# uC_Sensor.net
KiCad netlist of a schematic drawn in EAGLE
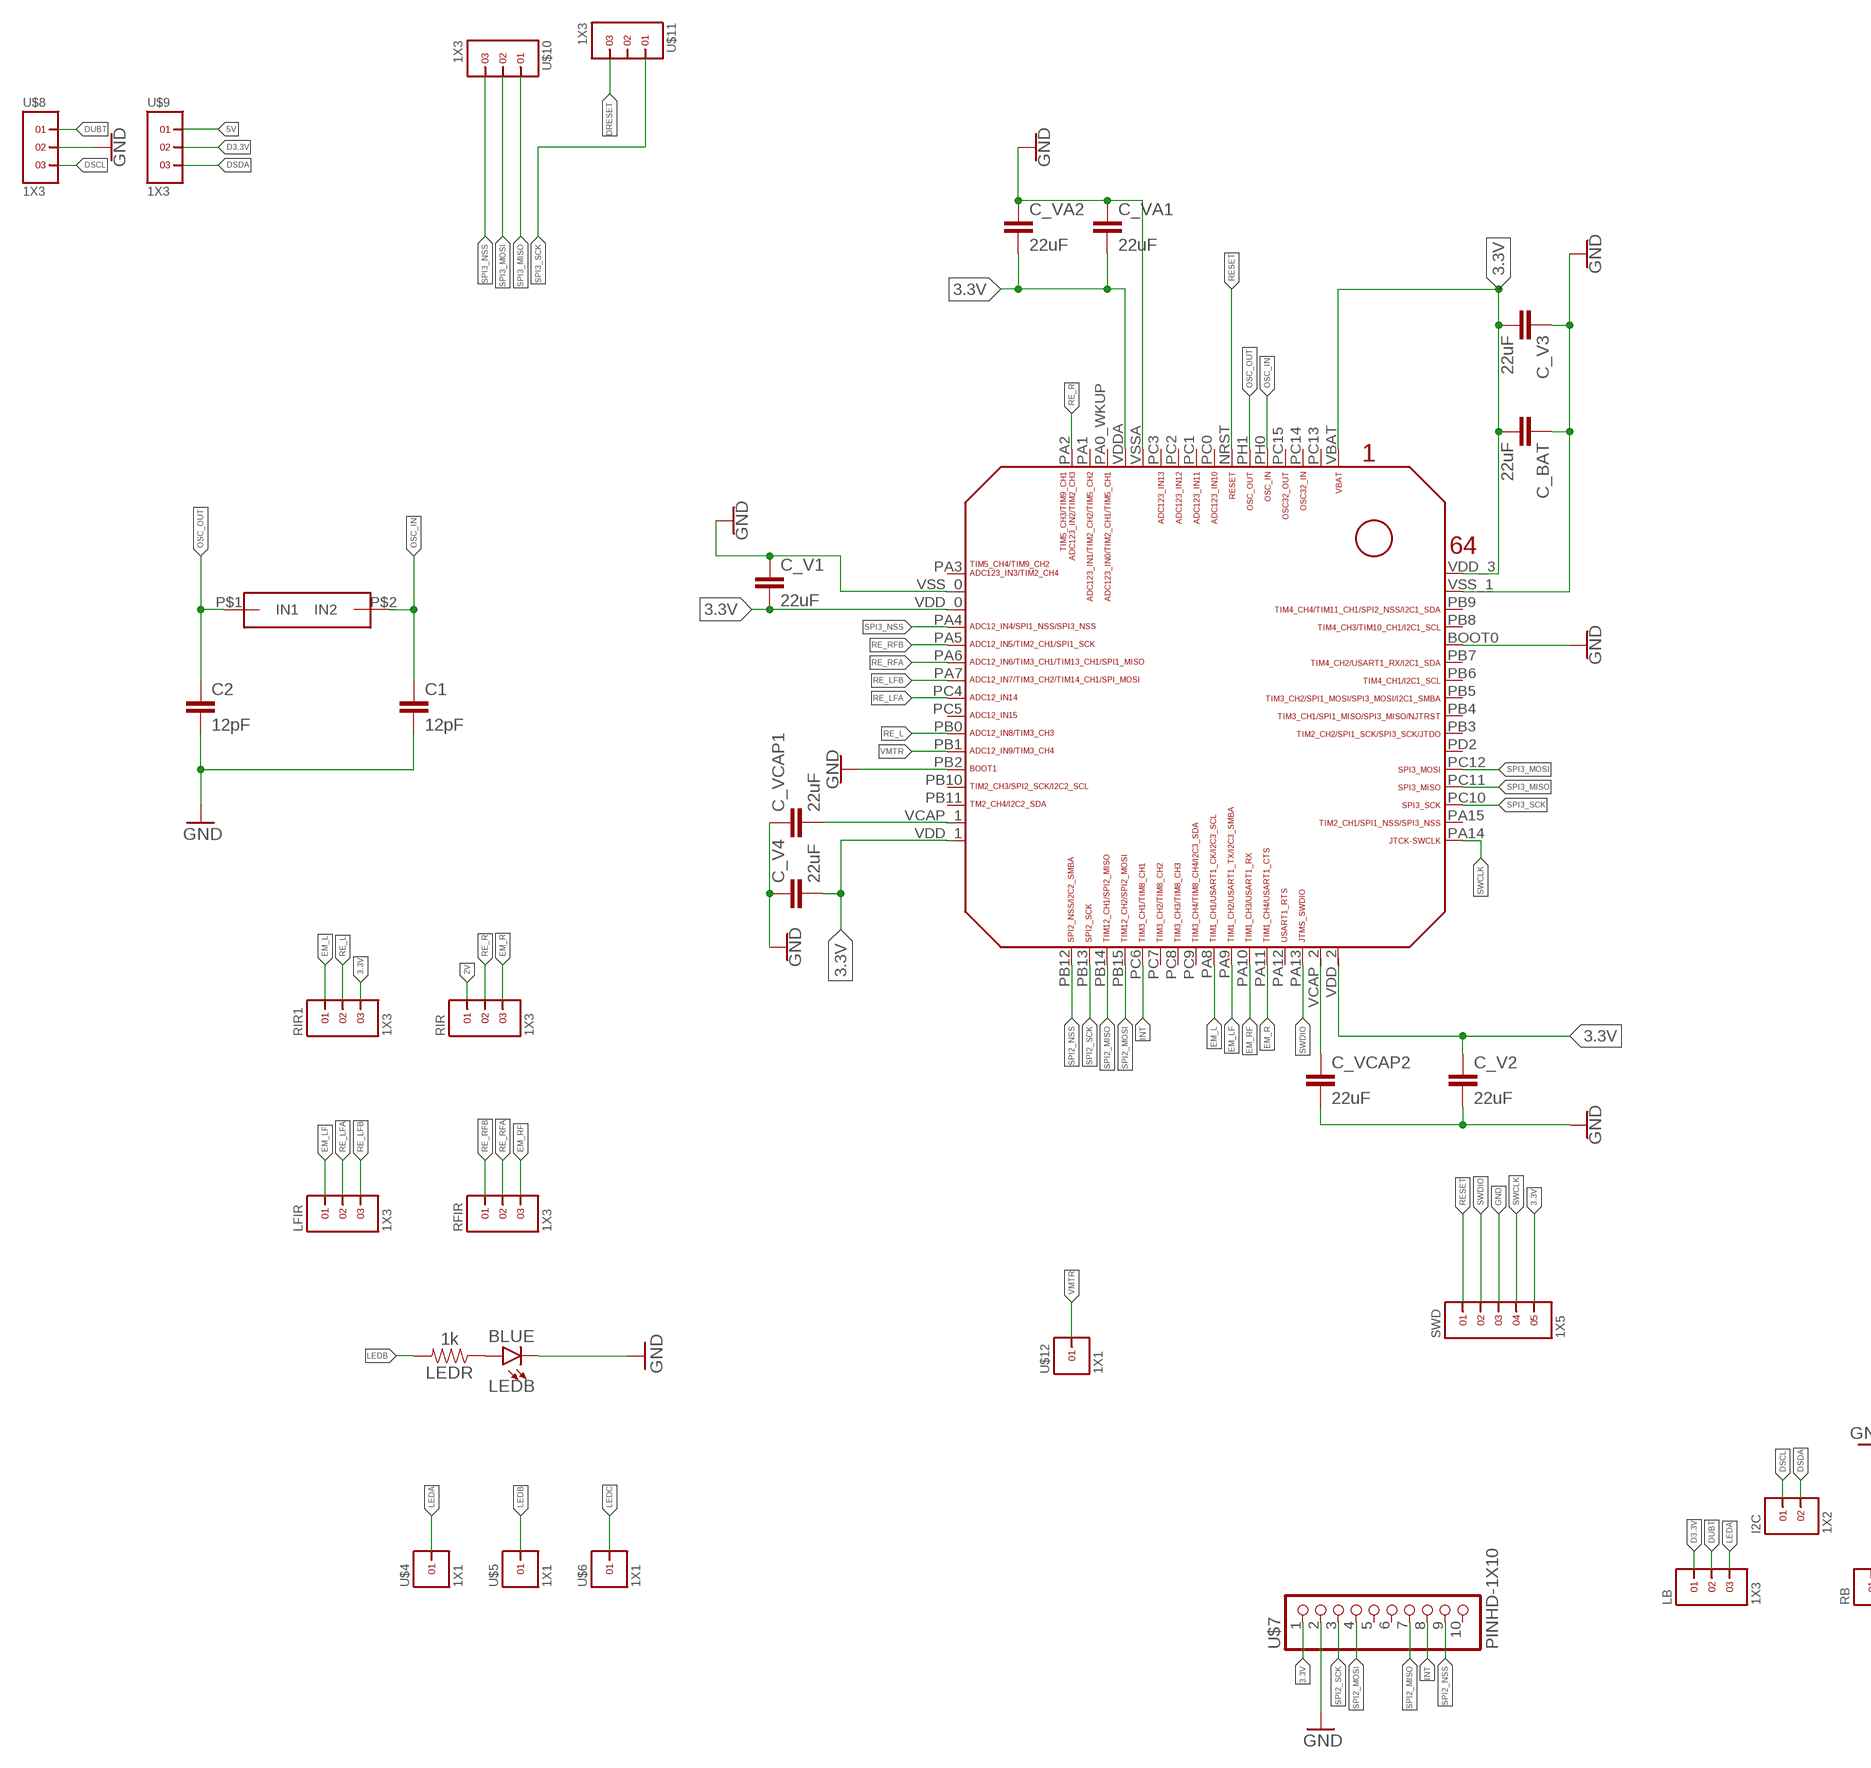
[diagram p0: schematic, sheet 1, part 1 of 2]
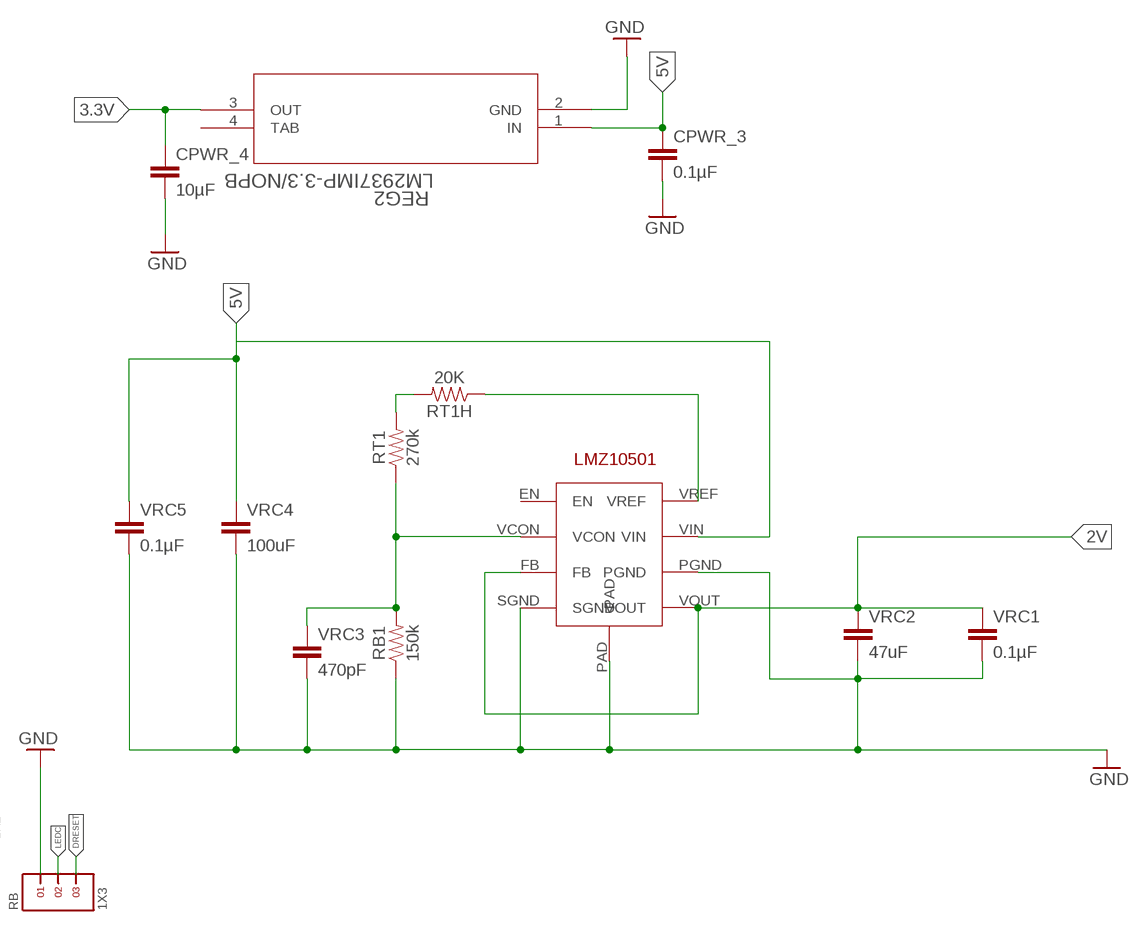
[diagram p1: schematic, sheet 1, part 2 of 2]

(export (version "E")
  (design (tool "Eeschema 10.0.6"))
  (components
    (comp (ref "C1")
      (value "12pF")
      (footprint "eagle-import:0603")
      (libsource (lib "eagle-import") (part "22PF-0603-50V-5%"))
    )
    (comp (ref "C2")
      (value "12pF")
      (footprint "eagle-import:0603")
      (libsource (lib "eagle-import") (part "22PF-0603-50V-5%"))
    )
    (comp (ref "CPWR_3")
      (value "0.1µF")
      (footprint "eagle-import:0805@2")
      (libsource (lib "eagle-import") (part "0.33UF/330NF-0805-50V-10%"))
    )
    (comp (ref "CPWR_4")
      (value "10µF")
      (footprint "eagle-import:0805@2")
      (libsource (lib "eagle-import") (part "0.33UF/330NF-0805-50V-10%"))
    )
    (comp (ref "C_BAT")
      (value "22uF")
      (footprint "eagle-import:0805")
      (libsource (lib "eagle-import") (part "22UF-0805-6.3V-20%"))
    )
    (comp (ref "C_V1")
      (value "22uF")
      (footprint "eagle-import:0805")
      (libsource (lib "eagle-import") (part "22UF-0805-6.3V-20%"))
    )
    (comp (ref "C_V2")
      (value "22uF")
      (footprint "eagle-import:0805")
      (libsource (lib "eagle-import") (part "22UF-0805-6.3V-20%"))
    )
    (comp (ref "C_V3")
      (value "22uF")
      (footprint "eagle-import:0805")
      (libsource (lib "eagle-import") (part "22UF-0805-6.3V-20%"))
    )
    (comp (ref "C_V4")
      (value "22uF")
      (footprint "eagle-import:0805")
      (libsource (lib "eagle-import") (part "22UF-0805-6.3V-20%"))
    )
    (comp (ref "C_VA1")
      (value "22uF")
      (footprint "eagle-import:0805")
      (libsource (lib "eagle-import") (part "22UF-0805-6.3V-20%"))
    )
    (comp (ref "C_VA2")
      (value "22uF")
      (footprint "eagle-import:0805")
      (libsource (lib "eagle-import") (part "22UF-0805-6.3V-20%"))
    )
    (comp (ref "C_VCAP1")
      (value "22uF")
      (footprint "eagle-import:0805")
      (libsource (lib "eagle-import") (part "22UF-0805-6.3V-20%"))
    )
    (comp (ref "C_VCAP2")
      (value "22uF")
      (footprint "eagle-import:0805")
      (libsource (lib "eagle-import") (part "22UF-0805-6.3V-20%"))
    )
    (comp (ref "I2C")
      (value "1X2")
      (footprint "eagle-import:1X2")
      (libsource (lib "eagle-import") (part "1X2"))
    )
    (comp (ref "LB")
      (value "1X3")
      (footprint "eagle-import:1X3")
      (libsource (lib "eagle-import") (part "1X3"))
    )
    (comp (ref "LEDB")
      (value "BLUE")
      (footprint "eagle-import:LED-1206")
      (libsource (lib "eagle-import") (part "LED-BLUE1206"))
    )
    (comp (ref "LEDR")
      (value "1k")
      (footprint "eagle-import:0805")
      (libsource (lib "eagle-import") (part "0.75OHM-0805-1/4W-1%"))
    )
    (comp (ref "LFIR")
      (value "1X3")
      (footprint "eagle-import:1X3")
      (libsource (lib "eagle-import") (part "1X3"))
    )
    (comp (ref "RB")
      (value "1X3")
      (footprint "eagle-import:1X3")
      (libsource (lib "eagle-import") (part "1X3"))
    )
    (comp (ref "RB1")
      (value "150k")
      (footprint "eagle-import:0805")
      (libsource (lib "eagle-import") (part "SparkFun-Resistors_532_0.75OHM-0805-1/4W-1%"))
    )
    (comp (ref "REG2")
      (value "LM2937IMP-3.3/NOPB")
      (footprint "eagle-import:MP04A")
      (fields
        (field (name "MANUFACTURER_PART_NUMBER") "lm2937imp3_3nopb")
        (field (name "COPYRIGHT") "Copyright C 2015 Accelerated Designs. All rights reserved")
      )
      (libsource (lib "eagle-import") (part "LM2937IMP-3.3/NOPB"))
    )
    (comp (ref "RFIR")
      (value "1X3")
      (footprint "eagle-import:1X3")
      (libsource (lib "eagle-import") (part "1X3"))
    )
    (comp (ref "RIR")
      (value "1X3")
      (footprint "eagle-import:1X3")
      (libsource (lib "eagle-import") (part "1X3"))
    )
    (comp (ref "RIR1")
      (value "1X3")
      (footprint "eagle-import:1X3")
      (libsource (lib "eagle-import") (part "1X3"))
    )
    (comp (ref "RT1")
      (value "270k")
      (footprint "eagle-import:0805")
      (libsource (lib "eagle-import") (part "SparkFun-Resistors_532_0.75OHM-0805-1/4W-1%"))
    )
    (comp (ref "RT1H")
      (value "20K")
      (footprint "eagle-import:0805")
      (libsource (lib "eagle-import") (part "SparkFun-Resistors_532_0.75OHM-0805-1/4W-1%"))
    )
    (comp (ref "SWD")
      (value "1X5")
      (footprint "eagle-import:1X5")
      (libsource (lib "eagle-import") (part "1X5"))
    )
    (comp (ref "U$1")
      (value "STM32F405/415_LQFP64")
      (footprint "eagle-import:STM32F405_415_LQFP64")
      (libsource (lib "eagle-import") (part "STM32F405/415_LQFP64"))
    )
    (comp (ref "U$2")
      (value "OSC")
      (footprint "eagle-import:OSC")
      (libsource (lib "eagle-import") (part "OSC"))
    )
    (comp (ref "U$3")
      (value "LMZ10501")
      (footprint "eagle-import:LMZ10501")
      (libsource (lib "eagle-import") (part "LMZ10501"))
    )
    (comp (ref "U$4")
      (value "1X1")
      (footprint "eagle-import:1X1")
      (libsource (lib "eagle-import") (part "1X1"))
    )
    (comp (ref "U$5")
      (value "1X1")
      (footprint "eagle-import:1X1")
      (libsource (lib "eagle-import") (part "1X1"))
    )
    (comp (ref "U$6")
      (value "1X1")
      (footprint "eagle-import:1X1")
      (libsource (lib "eagle-import") (part "1X1"))
    )
    (comp (ref "U$7")
      (value "PINHD-1X10")
      (footprint "eagle-import:1X10-BIG")
      (libsource (lib "eagle-import") (part "PINHD-1X10"))
    )
    (comp (ref "U$8")
      (value "1X3")
      (footprint "eagle-import:1X3")
      (libsource (lib "eagle-import") (part "1X3"))
    )
    (comp (ref "U$9")
      (value "1X3")
      (footprint "eagle-import:1X3")
      (libsource (lib "eagle-import") (part "1X3"))
    )
    (comp (ref "U$10")
      (value "1X3")
      (footprint "eagle-import:1X3")
      (libsource (lib "eagle-import") (part "1X3"))
    )
    (comp (ref "U$11")
      (value "1X3")
      (footprint "eagle-import:1X3")
      (libsource (lib "eagle-import") (part "1X3"))
    )
    (comp (ref "U$12")
      (value "1X1")
      (footprint "eagle-import:1X1")
      (libsource (lib "eagle-import") (part "1X1"))
    )
    (comp (ref "VRC1")
      (value "0.1µF")
      (footprint "eagle-import:0805@2")
      (libsource (lib "eagle-import") (part "0.33UF/330NF-0805-50V-10%"))
    )
    (comp (ref "VRC2")
      (value "47uF")
      (footprint "eagle-import:0805@2")
      (libsource (lib "eagle-import") (part "0.33UF/330NF-0805-50V-10%"))
    )
    (comp (ref "VRC3")
      (value "470pF")
      (footprint "eagle-import:0805@2")
      (libsource (lib "eagle-import") (part "0.33UF/330NF-0805-50V-10%"))
    )
    (comp (ref "VRC4")
      (value "100uF")
      (footprint "eagle-import:0805@2")
      (libsource (lib "eagle-import") (part "0.33UF/330NF-0805-50V-10%"))
    )
    (comp (ref "VRC5")
      (value "0.1µF")
      (footprint "eagle-import:0805@2")
      (libsource (lib "eagle-import") (part "0.33UF/330NF-0805-50V-10%"))
    )
  )
  (nets
    (net (code "1") (name "/TAB") (class "Default")
      (node (ref "REG2") (pin "4") (pinfunction "TAB_4") (pintype "power_in"))
    )
    (net (code "2") (name "2V") (class "Default")
      (node (ref "RIR") (pin "1") (pinfunction "1_1") (pintype "bidirectional"))
      (node (ref "U$3") (pin "FB") (pinfunction "FB_FB") (pintype "bidirectional"))
      (node (ref "U$3") (pin "VOUT") (pinfunction "VOUT_VOUT") (pintype "bidirectional"))
      (node (ref "VRC1") (pin "1") (pinfunction "1_1") (pintype "passive"))
      (node (ref "VRC2") (pin "1") (pinfunction "1_1") (pintype "passive"))
    )
    (net (code "3") (name "3.3V") (class "Default")
      (node (ref "CPWR_4") (pin "1") (pinfunction "1_1") (pintype "passive"))
      (node (ref "C_BAT") (pin "2") (pinfunction "2_2") (pintype "passive"))
      (node (ref "C_V1") (pin "2") (pinfunction "2_2") (pintype "passive"))
      (node (ref "C_V2") (pin "1") (pinfunction "1_1") (pintype "passive"))
      (node (ref "C_V3") (pin "2") (pinfunction "2_2") (pintype "passive"))
      (node (ref "C_V4") (pin "2") (pinfunction "2_2") (pintype "passive"))
      (node (ref "C_VA1") (pin "2") (pinfunction "2_2") (pintype "passive"))
      (node (ref "C_VA2") (pin "2") (pinfunction "2_2") (pintype "passive"))
      (node (ref "REG2") (pin "3") (pinfunction "OUT_3") (pintype "power_in"))
      (node (ref "RIR1") (pin "3") (pinfunction "3_3") (pintype "bidirectional"))
      (node (ref "SWD") (pin "5") (pinfunction "5_5") (pintype "bidirectional"))
      (node (ref "U$1") (pin "VBAT") (pinfunction "VBAT_VBAT") (pintype "bidirectional"))
      (node (ref "U$1") (pin "VDDA") (pinfunction "VDDA_VDDA") (pintype "bidirectional"))
      (node (ref "U$1") (pin "VDD_0") (pinfunction "VDD_0_VDD_0") (pintype "bidirectional"))
      (node (ref "U$1") (pin "VDD_1") (pinfunction "VDD_1_VDD_1") (pintype "bidirectional"))
      (node (ref "U$1") (pin "VDD_2") (pinfunction "VDD_2_VDD_2") (pintype "bidirectional"))
      (node (ref "U$1") (pin "VDD_3") (pinfunction "VDD_3_VDD_3") (pintype "bidirectional"))
      (node (ref "U$7") (pin "1") (pinfunction "1_1") (pintype "passive"))
    )
    (net (code "4") (name "5V") (class "Default")
      (node (ref "CPWR_3") (pin "1") (pinfunction "1_1") (pintype "passive"))
      (node (ref "REG2") (pin "1") (pinfunction "IN_1") (pintype "power_in"))
      (node (ref "U$3") (pin "VIN") (pinfunction "VIN_VIN") (pintype "bidirectional"))
      (node (ref "U$9") (pin "1") (pinfunction "1_1") (pintype "bidirectional"))
      (node (ref "VRC4") (pin "1") (pinfunction "1_1") (pintype "passive"))
      (node (ref "VRC5") (pin "1") (pinfunction "1_1") (pintype "passive"))
    )
    (net (code "5") (name "D3.3V") (class "Default")
      (node (ref "LB") (pin "1") (pinfunction "1_1") (pintype "bidirectional"))
      (node (ref "U$9") (pin "2") (pinfunction "2_2") (pintype "bidirectional"))
    )
    (net (code "6") (name "DRESET") (class "Default")
      (node (ref "RB") (pin "3") (pinfunction "3_3") (pintype "bidirectional"))
      (node (ref "U$11") (pin "3") (pinfunction "3_3") (pintype "bidirectional"))
    )
    (net (code "7") (name "DSCL") (class "Default")
      (node (ref "I2C") (pin "1") (pinfunction "1_1") (pintype "bidirectional"))
      (node (ref "U$8") (pin "3") (pinfunction "3_3") (pintype "bidirectional"))
    )
    (net (code "8") (name "DSDA") (class "Default")
      (node (ref "I2C") (pin "2") (pinfunction "2_2") (pintype "bidirectional"))
      (node (ref "U$9") (pin "3") (pinfunction "3_3") (pintype "bidirectional"))
    )
    (net (code "9") (name "DUBT") (class "Default")
      (node (ref "LB") (pin "2") (pinfunction "2_2") (pintype "bidirectional"))
      (node (ref "U$8") (pin "1") (pinfunction "1_1") (pintype "bidirectional"))
    )
    (net (code "10") (name "EM_L") (class "Default")
      (node (ref "RIR1") (pin "1") (pinfunction "1_1") (pintype "bidirectional"))
      (node (ref "U$1") (pin "PA8") (pinfunction "PA8_PA8") (pintype "bidirectional"))
    )
    (net (code "11") (name "EM_LF") (class "Default")
      (node (ref "LFIR") (pin "1") (pinfunction "1_1") (pintype "bidirectional"))
      (node (ref "U$1") (pin "PA9") (pinfunction "PA9_PA9") (pintype "bidirectional"))
    )
    (net (code "12") (name "EM_R") (class "Default")
      (node (ref "RIR") (pin "3") (pinfunction "3_3") (pintype "bidirectional"))
      (node (ref "U$1") (pin "PA11") (pinfunction "PA11_PA11") (pintype "bidirectional"))
    )
    (net (code "13") (name "EM_RF") (class "Default")
      (node (ref "RFIR") (pin "3") (pinfunction "3_3") (pintype "bidirectional"))
      (node (ref "U$1") (pin "PA10") (pinfunction "PA10_PA10") (pintype "bidirectional"))
    )
    (net (code "14") (name "GND") (class "Default")
      (node (ref "C1") (pin "2") (pinfunction "2_2") (pintype "passive"))
      (node (ref "C2") (pin "2") (pinfunction "2_2") (pintype "passive"))
      (node (ref "CPWR_3") (pin "2") (pinfunction "2_2") (pintype "passive"))
      (node (ref "CPWR_4") (pin "2") (pinfunction "2_2") (pintype "passive"))
      (node (ref "C_BAT") (pin "1") (pinfunction "1_1") (pintype "passive"))
      (node (ref "C_V1") (pin "1") (pinfunction "1_1") (pintype "passive"))
      (node (ref "C_V2") (pin "2") (pinfunction "2_2") (pintype "passive"))
      (node (ref "C_V3") (pin "1") (pinfunction "1_1") (pintype "passive"))
      (node (ref "C_V4") (pin "1") (pinfunction "1_1") (pintype "passive"))
      (node (ref "C_VA1") (pin "1") (pinfunction "1_1") (pintype "passive"))
      (node (ref "C_VA2") (pin "1") (pinfunction "1_1") (pintype "passive"))
      (node (ref "C_VCAP1") (pin "1") (pinfunction "1_1") (pintype "passive"))
      (node (ref "C_VCAP2") (pin "2") (pinfunction "2_2") (pintype "passive"))
      (node (ref "LEDB") (pin "C") (pinfunction "C_C") (pintype "passive"))
      (node (ref "RB") (pin "1") (pinfunction "1_1") (pintype "bidirectional"))
      (node (ref "RB1") (pin "1") (pinfunction "1_1") (pintype "passive"))
      (node (ref "REG2") (pin "2") (pinfunction "GND_2") (pintype "power_in"))
      (node (ref "SWD") (pin "3") (pinfunction "3_3") (pintype "bidirectional"))
      (node (ref "U$1") (pin "BOOT0") (pinfunction "BOOT0_BOOT0") (pintype "bidirectional"))
      (node (ref "U$1") (pin "PB2") (pinfunction "PB2_PB2") (pintype "bidirectional"))
      (node (ref "U$1") (pin "VSSA") (pinfunction "VSSA_VSSA") (pintype "bidirectional"))
      (node (ref "U$1") (pin "VSS_0") (pinfunction "VSS_0_VSS_0") (pintype "bidirectional"))
      (node (ref "U$1") (pin "VSS_1") (pinfunction "VSS_1_VSS_1") (pintype "bidirectional"))
      (node (ref "U$3") (pin "PAD") (pinfunction "PAD_PAD") (pintype "bidirectional"))
      (node (ref "U$3") (pin "PGND") (pinfunction "PGND_PGND") (pintype "bidirectional"))
      (node (ref "U$3") (pin "SGND") (pinfunction "SGND_SGND") (pintype "bidirectional"))
      (node (ref "U$7") (pin "2") (pinfunction "2_2") (pintype "passive"))
      (node (ref "U$8") (pin "2") (pinfunction "2_2") (pintype "bidirectional"))
      (node (ref "VRC1") (pin "2") (pinfunction "2_2") (pintype "passive"))
      (node (ref "VRC2") (pin "2") (pinfunction "2_2") (pintype "passive"))
      (node (ref "VRC3") (pin "2") (pinfunction "2_2") (pintype "passive"))
      (node (ref "VRC4") (pin "2") (pinfunction "2_2") (pintype "passive"))
      (node (ref "VRC5") (pin "2") (pinfunction "2_2") (pintype "passive"))
    )
    (net (code "15") (name "INT") (class "Default")
      (node (ref "U$1") (pin "PC6") (pinfunction "PC6_PC6") (pintype "bidirectional"))
      (node (ref "U$7") (pin "8") (pinfunction "8_8") (pintype "passive"))
    )
    (net (code "16") (name "LEDA") (class "Default")
      (node (ref "LB") (pin "3") (pinfunction "3_3") (pintype "bidirectional"))
      (node (ref "U$4") (pin "1") (pinfunction "1_1") (pintype "bidirectional"))
    )
    (net (code "17") (name "LEDB") (class "Default")
      (node (ref "LEDR") (pin "2") (pinfunction "2_2") (pintype "passive"))
      (node (ref "U$5") (pin "1") (pinfunction "1_1") (pintype "bidirectional"))
    )
    (net (code "18") (name "LEDC") (class "Default")
      (node (ref "RB") (pin "2") (pinfunction "2_2") (pintype "bidirectional"))
      (node (ref "U$6") (pin "1") (pinfunction "1_1") (pintype "bidirectional"))
    )
    (net (code "19") (name "Net-(C_VCAP1-Pad2)") (class "Default")
      (node (ref "C_VCAP1") (pin "2") (pinfunction "2_2") (pintype "passive"))
      (node (ref "U$1") (pin "VCAP_1") (pinfunction "VCAP_1_VCAP_1") (pintype "bidirectional"))
    )
    (net (code "20") (name "Net-(C_VCAP2-Pad1)") (class "Default")
      (node (ref "C_VCAP2") (pin "1") (pinfunction "1_1") (pintype "passive"))
      (node (ref "U$1") (pin "VCAP_2") (pinfunction "VCAP_2_VCAP_2") (pintype "bidirectional"))
    )
    (net (code "21") (name "Net-(LEDB-PadA)") (class "Default")
      (node (ref "LEDB") (pin "A") (pinfunction "A_A") (pintype "passive"))
      (node (ref "LEDR") (pin "1") (pinfunction "1_1") (pintype "passive"))
    )
    (net (code "22") (name "Net-(RB1-Pad2)") (class "Default")
      (node (ref "RB1") (pin "2") (pinfunction "2_2") (pintype "passive"))
      (node (ref "RT1") (pin "1") (pinfunction "1_1") (pintype "passive"))
      (node (ref "U$3") (pin "VCON") (pinfunction "VCON_VCON") (pintype "bidirectional"))
      (node (ref "VRC3") (pin "1") (pinfunction "1_1") (pintype "passive"))
    )
    (net (code "23") (name "Net-(RT1-Pad2)") (class "Default")
      (node (ref "RT1") (pin "2") (pinfunction "2_2") (pintype "passive"))
      (node (ref "RT1H") (pin "2") (pinfunction "2_2") (pintype "passive"))
    )
    (net (code "24") (name "Net-(RT1H-Pad1)") (class "Default")
      (node (ref "RT1H") (pin "1") (pinfunction "1_1") (pintype "passive"))
      (node (ref "U$3") (pin "VREF") (pinfunction "VREF_VREF") (pintype "bidirectional"))
    )
    (net (code "25") (name "OSC_IN") (class "Default")
      (node (ref "C1") (pin "1") (pinfunction "1_1") (pintype "passive"))
      (node (ref "U$1") (pin "PH0") (pinfunction "PH0_PH0") (pintype "bidirectional"))
      (node (ref "U$2") (pin "P$2") (pinfunction "IN2_P$2") (pintype "bidirectional"))
    )
    (net (code "26") (name "OSC_OUT") (class "Default")
      (node (ref "C2") (pin "1") (pinfunction "1_1") (pintype "passive"))
      (node (ref "U$1") (pin "PH1") (pinfunction "PH1_PH1") (pintype "bidirectional"))
      (node (ref "U$2") (pin "P$1") (pinfunction "IN1_P$1") (pintype "bidirectional"))
    )
    (net (code "27") (name "RESET") (class "Default")
      (node (ref "SWD") (pin "1") (pinfunction "1_1") (pintype "bidirectional"))
      (node (ref "U$1") (pin "NRST") (pinfunction "NRST_NRST") (pintype "bidirectional"))
    )
    (net (code "28") (name "RE_L") (class "Default")
      (node (ref "RIR1") (pin "2") (pinfunction "2_2") (pintype "bidirectional"))
      (node (ref "U$1") (pin "PB0") (pinfunction "PB0_PB0") (pintype "bidirectional"))
    )
    (net (code "29") (name "RE_LFA") (class "Default")
      (node (ref "LFIR") (pin "2") (pinfunction "2_2") (pintype "bidirectional"))
      (node (ref "U$1") (pin "PC4") (pinfunction "PC4_PC4") (pintype "bidirectional"))
    )
    (net (code "30") (name "RE_LFB") (class "Default")
      (node (ref "LFIR") (pin "3") (pinfunction "3_3") (pintype "bidirectional"))
      (node (ref "U$1") (pin "PA7") (pinfunction "PA7_PA7") (pintype "bidirectional"))
    )
    (net (code "31") (name "RE_R") (class "Default")
      (node (ref "RIR") (pin "2") (pinfunction "2_2") (pintype "bidirectional"))
      (node (ref "U$1") (pin "PA2") (pinfunction "PA2_PA2") (pintype "bidirectional"))
    )
    (net (code "32") (name "RE_RFA") (class "Default")
      (node (ref "RFIR") (pin "2") (pinfunction "2_2") (pintype "bidirectional"))
      (node (ref "U$1") (pin "PA6") (pinfunction "PA6_PA6") (pintype "bidirectional"))
    )
    (net (code "33") (name "RE_RFB") (class "Default")
      (node (ref "RFIR") (pin "1") (pinfunction "1_1") (pintype "bidirectional"))
      (node (ref "U$1") (pin "PA5") (pinfunction "PA5_PA5") (pintype "bidirectional"))
    )
    (net (code "34") (name "SPI2_MISO") (class "Default")
      (node (ref "U$1") (pin "PB14") (pinfunction "PB14_PB14") (pintype "bidirectional"))
      (node (ref "U$7") (pin "7") (pinfunction "7_7") (pintype "passive"))
    )
    (net (code "35") (name "SPI2_MOSI") (class "Default")
      (node (ref "U$1") (pin "PB15") (pinfunction "PB15_PB15") (pintype "bidirectional"))
      (node (ref "U$7") (pin "4") (pinfunction "4_4") (pintype "passive"))
    )
    (net (code "36") (name "SPI2_NSS") (class "Default")
      (node (ref "U$1") (pin "PB12") (pinfunction "PB12_PB12") (pintype "bidirectional"))
      (node (ref "U$7") (pin "9") (pinfunction "9_9") (pintype "passive"))
    )
    (net (code "37") (name "SPI2_SCK") (class "Default")
      (node (ref "U$1") (pin "PB13") (pinfunction "PB13_PB13") (pintype "bidirectional"))
      (node (ref "U$7") (pin "3") (pinfunction "3_3") (pintype "passive"))
    )
    (net (code "38") (name "SPI3_MISO") (class "Default")
      (node (ref "U$1") (pin "PC11") (pinfunction "PC11_PC11") (pintype "bidirectional"))
      (node (ref "U$10") (pin "1") (pinfunction "1_1") (pintype "bidirectional"))
    )
    (net (code "39") (name "SPI3_MOSI") (class "Default")
      (node (ref "U$1") (pin "PC12") (pinfunction "PC12_PC12") (pintype "bidirectional"))
      (node (ref "U$10") (pin "2") (pinfunction "2_2") (pintype "bidirectional"))
    )
    (net (code "40") (name "SPI3_NSS") (class "Default")
      (node (ref "U$1") (pin "PA4") (pinfunction "PA4_PA4") (pintype "bidirectional"))
      (node (ref "U$10") (pin "3") (pinfunction "3_3") (pintype "bidirectional"))
    )
    (net (code "41") (name "SPI3_SCK") (class "Default")
      (node (ref "U$1") (pin "PC10") (pinfunction "PC10_PC10") (pintype "bidirectional"))
      (node (ref "U$11") (pin "1") (pinfunction "1_1") (pintype "bidirectional"))
    )
    (net (code "42") (name "SWCLK") (class "Default")
      (node (ref "SWD") (pin "4") (pinfunction "4_4") (pintype "bidirectional"))
      (node (ref "U$1") (pin "PA14") (pinfunction "PA14_PA14") (pintype "bidirectional"))
    )
    (net (code "43") (name "SWDIO") (class "Default")
      (node (ref "SWD") (pin "2") (pinfunction "2_2") (pintype "bidirectional"))
      (node (ref "U$1") (pin "PA13") (pinfunction "PA13_PA13") (pintype "bidirectional"))
    )
    (net (code "44") (name "VMTR") (class "Default")
      (node (ref "U$1") (pin "PB1") (pinfunction "PB1_PB1") (pintype "bidirectional"))
      (node (ref "U$12") (pin "1") (pinfunction "1_1") (pintype "bidirectional"))
    )
    (net (code "45") (name "unconnected-(U$1-PA0_AKUP-PadPA0_WKUP)") (class "Default")
      (node (ref "U$1") (pin "PA0_WKUP") (pinfunction "PA0_AKUP_PA0_WKUP") (pintype "bidirectional"))
    )
    (net (code "46") (name "unconnected-(U$1-PadPA1)") (class "Default")
      (node (ref "U$1") (pin "PA1") (pinfunction "PA1_PA1") (pintype "bidirectional"))
    )
    (net (code "47") (name "unconnected-(U$1-PadPA3)") (class "Default")
      (node (ref "U$1") (pin "PA3") (pinfunction "PA3_PA3") (pintype "bidirectional"))
    )
    (net (code "48") (name "unconnected-(U$1-PadPA12)") (class "Default")
      (node (ref "U$1") (pin "PA12") (pinfunction "PA12_PA12") (pintype "bidirectional"))
    )
    (net (code "49") (name "unconnected-(U$1-PadPA15)") (class "Default")
      (node (ref "U$1") (pin "PA15") (pinfunction "PA15_PA15") (pintype "bidirectional"))
    )
    (net (code "50") (name "unconnected-(U$1-PadPB3)") (class "Default")
      (node (ref "U$1") (pin "PB3") (pinfunction "PB3_PB3") (pintype "bidirectional"))
    )
    (net (code "51") (name "unconnected-(U$1-PadPB4)") (class "Default")
      (node (ref "U$1") (pin "PB4") (pinfunction "PB4_PB4") (pintype "bidirectional"))
    )
    (net (code "52") (name "unconnected-(U$1-PadPB5)") (class "Default")
      (node (ref "U$1") (pin "PB5") (pinfunction "PB5_PB5") (pintype "bidirectional"))
    )
    (net (code "53") (name "unconnected-(U$1-PadPB6)") (class "Default")
      (node (ref "U$1") (pin "PB6") (pinfunction "PB6_PB6") (pintype "bidirectional"))
    )
    (net (code "54") (name "unconnected-(U$1-PadPB7)") (class "Default")
      (node (ref "U$1") (pin "PB7") (pinfunction "PB7_PB7") (pintype "bidirectional"))
    )
    (net (code "55") (name "unconnected-(U$1-PadPB8)") (class "Default")
      (node (ref "U$1") (pin "PB8") (pinfunction "PB8_PB8") (pintype "bidirectional"))
    )
    (net (code "56") (name "unconnected-(U$1-PadPB9)") (class "Default")
      (node (ref "U$1") (pin "PB9") (pinfunction "PB9_PB9") (pintype "bidirectional"))
    )
    (net (code "57") (name "unconnected-(U$1-PadPB10)") (class "Default")
      (node (ref "U$1") (pin "PB10") (pinfunction "PB10_PB10") (pintype "bidirectional"))
    )
    (net (code "58") (name "unconnected-(U$1-PadPB11)") (class "Default")
      (node (ref "U$1") (pin "PB11") (pinfunction "PB11_PB11") (pintype "bidirectional"))
    )
    (net (code "59") (name "unconnected-(U$1-PadPC0)") (class "Default")
      (node (ref "U$1") (pin "PC0") (pinfunction "PC0_PC0") (pintype "bidirectional"))
    )
    (net (code "60") (name "unconnected-(U$1-PadPC1)") (class "Default")
      (node (ref "U$1") (pin "PC1") (pinfunction "PC1_PC1") (pintype "bidirectional"))
    )
    (net (code "61") (name "unconnected-(U$1-PadPC2)") (class "Default")
      (node (ref "U$1") (pin "PC2") (pinfunction "PC2_PC2") (pintype "bidirectional"))
    )
    (net (code "62") (name "unconnected-(U$1-PadPC3)") (class "Default")
      (node (ref "U$1") (pin "PC3") (pinfunction "PC3_PC3") (pintype "bidirectional"))
    )
    (net (code "63") (name "unconnected-(U$1-PadPC5)") (class "Default")
      (node (ref "U$1") (pin "PC5") (pinfunction "PC5_PC5") (pintype "bidirectional"))
    )
    (net (code "64") (name "unconnected-(U$1-PadPC7)") (class "Default")
      (node (ref "U$1") (pin "PC7") (pinfunction "PC7_PC7") (pintype "bidirectional"))
    )
    (net (code "65") (name "unconnected-(U$1-PadPC8)") (class "Default")
      (node (ref "U$1") (pin "PC8") (pinfunction "PC8_PC8") (pintype "bidirectional"))
    )
    (net (code "66") (name "unconnected-(U$1-PadPC9)") (class "Default")
      (node (ref "U$1") (pin "PC9") (pinfunction "PC9_PC9") (pintype "bidirectional"))
    )
    (net (code "67") (name "unconnected-(U$1-PadPC13)") (class "Default")
      (node (ref "U$1") (pin "PC13") (pinfunction "PC13_PC13") (pintype "bidirectional"))
    )
    (net (code "68") (name "unconnected-(U$1-PadPC14)") (class "Default")
      (node (ref "U$1") (pin "PC14") (pinfunction "PC14_PC14") (pintype "bidirectional"))
    )
    (net (code "69") (name "unconnected-(U$1-PadPC15)") (class "Default")
      (node (ref "U$1") (pin "PC15") (pinfunction "PC15_PC15") (pintype "bidirectional"))
    )
    (net (code "70") (name "unconnected-(U$1-PadPD2)") (class "Default")
      (node (ref "U$1") (pin "PD2") (pinfunction "PD2_PD2") (pintype "bidirectional"))
    )
    (net (code "71") (name "unconnected-(U$3-PadEN)") (class "Default")
      (node (ref "U$3") (pin "EN") (pinfunction "EN_EN") (pintype "bidirectional"))
    )
    (net (code "72") (name "unconnected-(U$7-Pad5)") (class "Default")
      (node (ref "U$7") (pin "5") (pinfunction "5_5") (pintype "passive"))
    )
    (net (code "73") (name "unconnected-(U$7-Pad6)") (class "Default")
      (node (ref "U$7") (pin "6") (pinfunction "6_6") (pintype "passive"))
    )
    (net (code "74") (name "unconnected-(U$7-Pad10)") (class "Default")
      (node (ref "U$7") (pin "10") (pinfunction "10_10") (pintype "passive"))
    )
    (net (code "75") (name "unconnected-(U$11-Pad2)") (class "Default")
      (node (ref "U$11") (pin "2") (pinfunction "2_2") (pintype "bidirectional"))
    )
  )
)
